# 1WB_DS2406_PROTECTED.net
KiCad netlist of a schematic drawn in Altium Designer
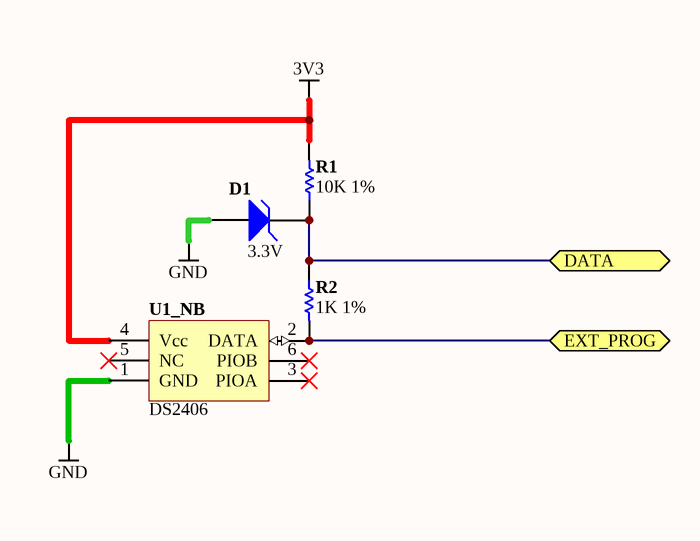
[diagram p0: 1WB_DS2406_PROTECTED.SchDoc]

(export (version "E")
  (design (tool "Eeschema 10.0.6"))
  (components
    (comp (ref "D1")
      (value "3.3V")
      (footprint "SOT95P230-3D")
      (description "Zener Diode, 3.3V")
      (libsource (lib "altium-import") (part "root_0_DIO-ZENER-1-3_"))
    )
    (comp (ref "R1")
      (value "10K 1%")
      (footprint "RESC1005-STAR")
      (description "Resistor, 10K 1% 0402 (1005)")
      (fields (field (name "TOLERANCE") "1 %"))
      (libsource (lib "altium-import") (part "root_2_RES_"))
    )
    (comp (ref "R2")
      (value "1K 1%")
      (footprint "RESC1005-STAR")
      (description "Resistor, 1K 1% 0402 (1005)")
      (fields (field (name "TOLERANCE") "1 %"))
      (libsource (lib "altium-import") (part "root_0_RES_"))
    )
    (comp (ref "U1_NB")
      (value "DS2406")
      (footprint "TSOC6")
      (description "Dual Addressable Switch Plus 1KB Memory")
      (fields (field (name "PUBLISHER") "Altium Limited"))
      (libsource (lib "altium-import") (part "root_0_DS2406_"))
    )
  )
  (nets
    (net (code "1") (name "/DATA") (class "Default")
      (node (ref "D1") (pin "2") (pinfunction "K_2") (pintype "passive"))
      (node (ref "R1") (pin "1") (pinfunction "1_1") (pintype "passive"))
      (node (ref "R2") (pin "1") (pinfunction "1_1") (pintype "passive"))
    )
    (net (code "2") (name "/EXT_PROG") (class "Default")
      (node (ref "R2") (pin "2") (pinfunction "2_2") (pintype "passive"))
      (node (ref "U1_NB") (pin "2") (pinfunction "DATA_2") (pintype "bidirectional"))
    )
    (net (code "3") (name "3V3") (class "Default")
      (node (ref "R1") (pin "2") (pinfunction "2_2") (pintype "passive"))
      (node (ref "U1_NB") (pin "4") (pinfunction "Vcc_4") (pintype "passive"))
    )
    (net (code "4") (name "GND") (class "Default")
      (node (ref "D1") (pin "1") (pinfunction "A_1") (pintype "passive"))
      (node (ref "U1_NB") (pin "1") (pinfunction "GND_1") (pintype "power_in"))
    )
    (net (code "5") (name "unconnected-(U1_NB-NC-Pad5)") (class "Default")
      (node (ref "U1_NB") (pin "5") (pinfunction "NC_5") (pintype "passive+no_connect"))
    )
    (net (code "6") (name "unconnected-(U1_NB-PIOA-Pad3)") (class "Default")
      (node (ref "U1_NB") (pin "3") (pinfunction "PIOA_3") (pintype "open_collector+no_connect"))
    )
    (net (code "7") (name "unconnected-(U1_NB-PIOB-Pad6)") (class "Default")
      (node (ref "U1_NB") (pin "6") (pinfunction "PIOB_6") (pintype "passive+no_connect"))
    )
  )
)
